# Aux_Board_V1.net
KiCad netlist of a schematic drawn in EAGLE
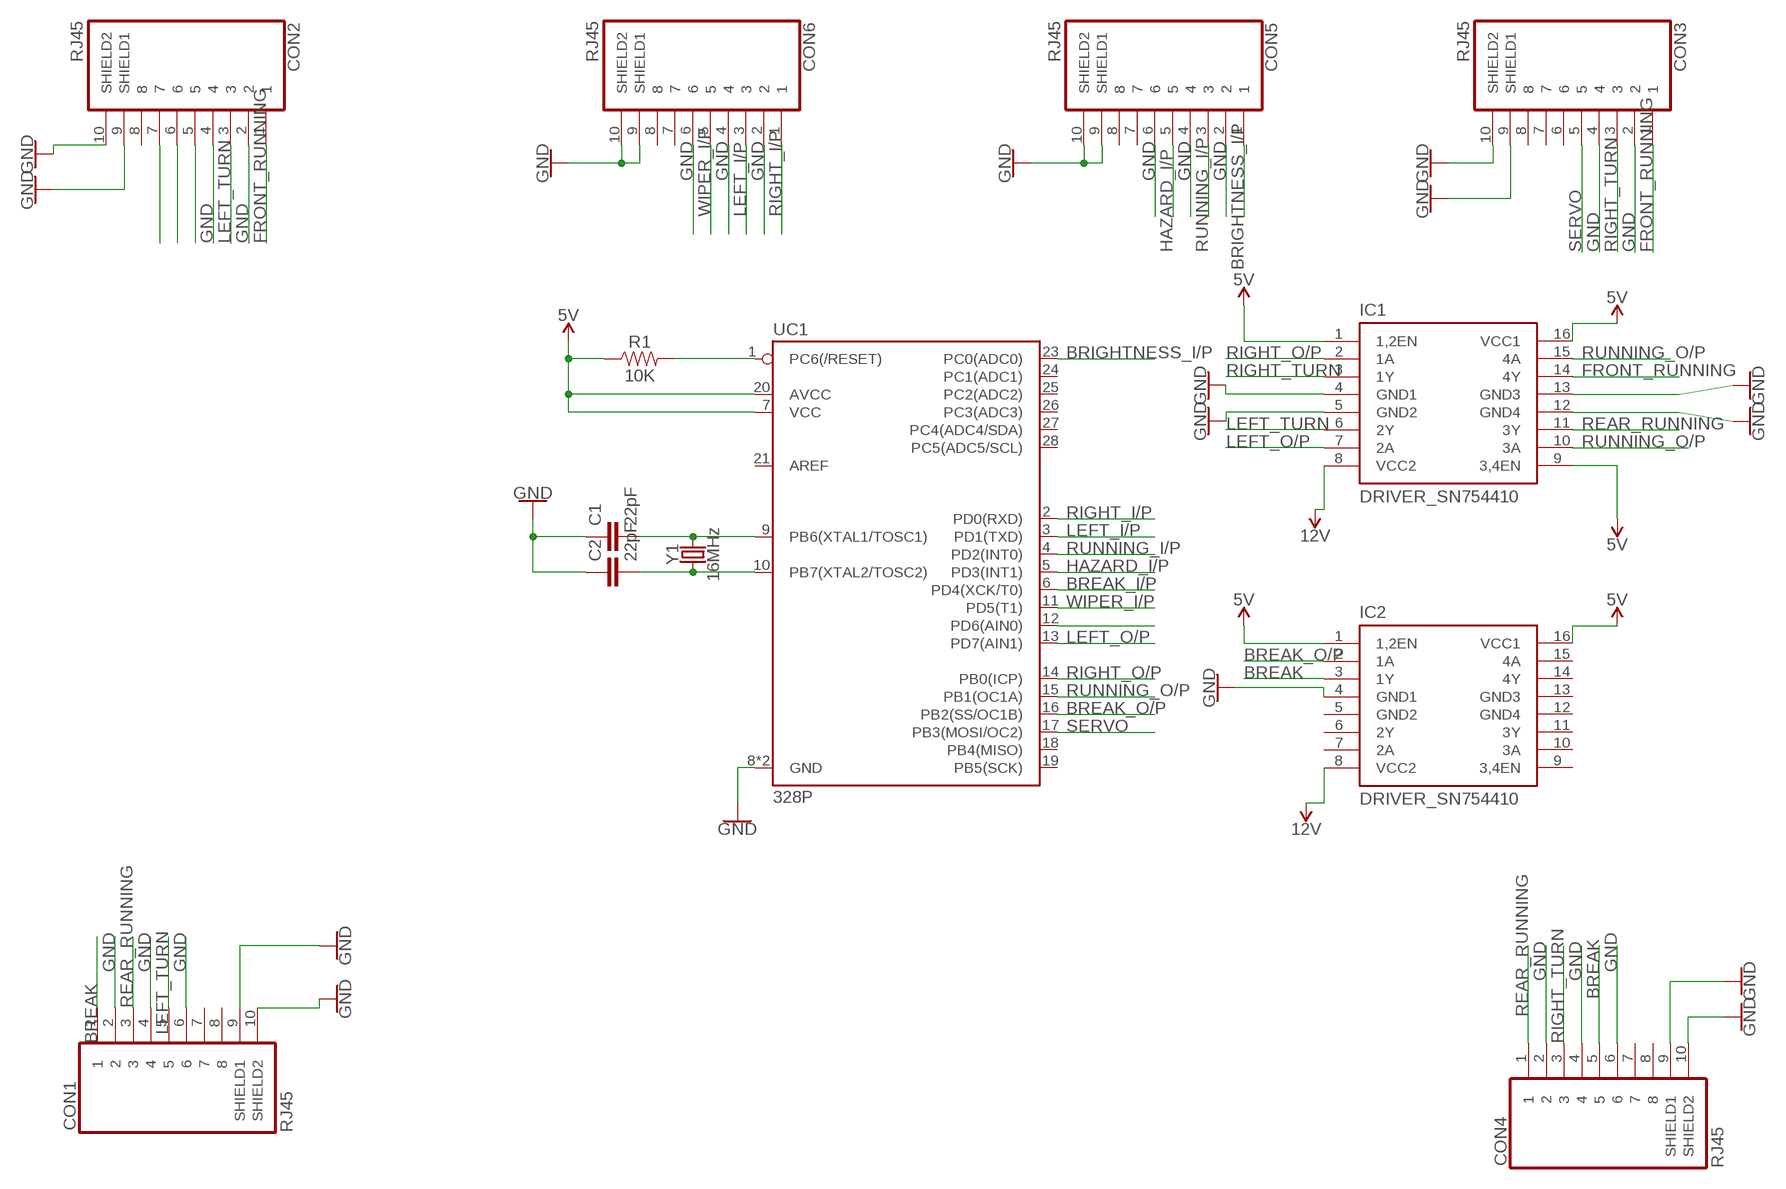
[diagram p0: schematic, sheet 1]

(export (version "E")
  (design (tool "Eeschema 10.0.6"))
  (components
    (comp (ref "C1")
      (value "22pF")
      (footprint "eagle-import:0805")
      (libsource (lib "eagle-import") (part "CAPACITOR_0805"))
    )
    (comp (ref "C2")
      (value "22pF")
      (footprint "eagle-import:0805")
      (libsource (lib "eagle-import") (part "CAPACITOR_0805"))
    )
    (comp (ref "CON1")
      (value "RJ45")
      (footprint "eagle-import:RJ45")
      (libsource (lib "eagle-import") (part "RJ45"))
    )
    (comp (ref "CON2")
      (value "RJ45")
      (footprint "eagle-import:RJ45")
      (libsource (lib "eagle-import") (part "RJ45"))
    )
    (comp (ref "CON3")
      (value "RJ45")
      (footprint "eagle-import:RJ45")
      (libsource (lib "eagle-import") (part "RJ45"))
    )
    (comp (ref "CON4")
      (value "RJ45")
      (footprint "eagle-import:RJ45")
      (libsource (lib "eagle-import") (part "RJ45"))
    )
    (comp (ref "CON5")
      (value "RJ45")
      (footprint "eagle-import:RJ45")
      (libsource (lib "eagle-import") (part "RJ45"))
    )
    (comp (ref "CON6")
      (value "RJ45")
      (footprint "eagle-import:RJ45")
      (libsource (lib "eagle-import") (part "RJ45"))
    )
    (comp (ref "IC1")
      (value "DRIVER_SN754410")
      (footprint "eagle-import:DIP16")
      (libsource (lib "eagle-import") (part "DRIVER_SN754410"))
    )
    (comp (ref "IC2")
      (value "DRIVER_SN754410")
      (footprint "eagle-import:DIP16")
      (libsource (lib "eagle-import") (part "DRIVER_SN754410"))
    )
    (comp (ref "R1")
      (value "10K")
      (footprint "eagle-import:0805")
      (libsource (lib "eagle-import") (part "RESISTOR_0805"))
    )
    (comp (ref "UC1")
      (value "328P")
      (footprint "eagle-import:DIP28")
      (libsource (lib "eagle-import") (part "ATMEGA328P_DIP28"))
    )
    (comp (ref "Y1")
      (value "16MHz")
      (footprint "eagle-import:HC49US")
      (libsource (lib "eagle-import") (part "CRYSTAL-16MHZPTH-HC49US"))
    )
  )
  (nets
    (net (code "1") (name "/BREAK") (class "Default")
      (node (ref "CON1") (pin "1") (pinfunction "1_1") (pintype "passive"))
      (node (ref "CON4") (pin "5") (pinfunction "5_5") (pintype "passive"))
      (node (ref "IC2") (pin "3") (pinfunction "1Y_3") (pintype "bidirectional"))
    )
    (net (code "2") (name "/BREAK_I{slash}P") (class "Default")
      (node (ref "UC1") (pin "6") (pinfunction "PD4(XCK/T0)_6") (pintype "bidirectional"))
    )
    (net (code "3") (name "/BREAK_O{slash}P") (class "Default")
      (node (ref "IC2") (pin "2") (pinfunction "1A_2") (pintype "bidirectional"))
      (node (ref "UC1") (pin "16") (pinfunction "PB2(SS/OC1B)_16") (pintype "bidirectional"))
    )
    (net (code "4") (name "/BRIGHTNESS_I{slash}P") (class "Default")
      (node (ref "CON5") (pin "1") (pinfunction "1_1") (pintype "passive"))
      (node (ref "UC1") (pin "23") (pinfunction "PC0(ADC0)_23") (pintype "bidirectional"))
    )
    (net (code "5") (name "/FRONT_RUNNING") (class "Default")
      (node (ref "CON2") (pin "1") (pinfunction "1_1") (pintype "passive"))
      (node (ref "CON3") (pin "1") (pinfunction "1_1") (pintype "passive"))
      (node (ref "IC1") (pin "14") (pinfunction "4Y_14") (pintype "bidirectional"))
    )
    (net (code "6") (name "/HAZARD_I{slash}P") (class "Default")
      (node (ref "CON5") (pin "5") (pinfunction "5_5") (pintype "passive"))
      (node (ref "UC1") (pin "5") (pinfunction "PD3(INT1)_5") (pintype "bidirectional"))
    )
    (net (code "7") (name "/LEFT_I{slash}P") (class "Default")
      (node (ref "CON6") (pin "3") (pinfunction "3_3") (pintype "passive"))
      (node (ref "UC1") (pin "3") (pinfunction "PD1(TXD)_3") (pintype "bidirectional"))
    )
    (net (code "8") (name "/LEFT_O{slash}P") (class "Default")
      (node (ref "IC1") (pin "7") (pinfunction "2A_7") (pintype "bidirectional"))
      (node (ref "UC1") (pin "13") (pinfunction "PD7(AIN1)_13") (pintype "bidirectional"))
    )
    (net (code "9") (name "/LEFT_TURN") (class "Default")
      (node (ref "CON1") (pin "5") (pinfunction "5_5") (pintype "passive"))
      (node (ref "CON2") (pin "3") (pinfunction "3_3") (pintype "passive"))
      (node (ref "IC1") (pin "6") (pinfunction "2Y_6") (pintype "bidirectional"))
    )
    (net (code "10") (name "/REAR_RUNNING") (class "Default")
      (node (ref "CON1") (pin "3") (pinfunction "3_3") (pintype "passive"))
      (node (ref "CON4") (pin "1") (pinfunction "1_1") (pintype "passive"))
      (node (ref "IC1") (pin "11") (pinfunction "3Y_11") (pintype "bidirectional"))
    )
    (net (code "11") (name "/RIGHT_I{slash}P") (class "Default")
      (node (ref "CON6") (pin "1") (pinfunction "1_1") (pintype "passive"))
      (node (ref "UC1") (pin "2") (pinfunction "PD0(RXD)_2") (pintype "bidirectional"))
    )
    (net (code "12") (name "/RIGHT_O{slash}P") (class "Default")
      (node (ref "IC1") (pin "2") (pinfunction "1A_2") (pintype "bidirectional"))
      (node (ref "UC1") (pin "14") (pinfunction "PB0(ICP)_14") (pintype "bidirectional"))
    )
    (net (code "13") (name "/RIGHT_TURN") (class "Default")
      (node (ref "CON3") (pin "3") (pinfunction "3_3") (pintype "passive"))
      (node (ref "CON4") (pin "3") (pinfunction "3_3") (pintype "passive"))
      (node (ref "IC1") (pin "3") (pinfunction "1Y_3") (pintype "bidirectional"))
    )
    (net (code "14") (name "/RUNNING_I{slash}P") (class "Default")
      (node (ref "CON5") (pin "3") (pinfunction "3_3") (pintype "passive"))
      (node (ref "UC1") (pin "4") (pinfunction "PD2(INT0)_4") (pintype "bidirectional"))
    )
    (net (code "15") (name "/RUNNING_O{slash}P") (class "Default")
      (node (ref "IC1") (pin "10") (pinfunction "3A_10") (pintype "bidirectional"))
      (node (ref "IC1") (pin "15") (pinfunction "4A_15") (pintype "bidirectional"))
      (node (ref "UC1") (pin "15") (pinfunction "PB1(OC1A)_15") (pintype "bidirectional"))
    )
    (net (code "16") (name "/SERVO") (class "Default")
      (node (ref "CON3") (pin "5") (pinfunction "5_5") (pintype "passive"))
      (node (ref "UC1") (pin "17") (pinfunction "PB3(MOSI/OC2)_17") (pintype "bidirectional"))
    )
    (net (code "17") (name "/WIPER_I{slash}P") (class "Default")
      (node (ref "CON6") (pin "5") (pinfunction "5_5") (pintype "passive"))
      (node (ref "UC1") (pin "11") (pinfunction "PD5(T1)_11") (pintype "bidirectional"))
    )
    (net (code "18") (name "5V") (class "Default")
      (node (ref "IC1") (pin "1") (pinfunction "1,2EN_1") (pintype "bidirectional"))
      (node (ref "IC1") (pin "16") (pinfunction "VCC1_16") (pintype "bidirectional"))
      (node (ref "IC1") (pin "9") (pinfunction "3,4EN_9") (pintype "bidirectional"))
      (node (ref "IC2") (pin "1") (pinfunction "1,2EN_1") (pintype "bidirectional"))
      (node (ref "IC2") (pin "16") (pinfunction "VCC1_16") (pintype "bidirectional"))
      (node (ref "R1") (pin "1") (pinfunction "1_1") (pintype "passive"))
      (node (ref "UC1") (pin "20") (pinfunction "AVCC_20") (pintype "bidirectional"))
      (node (ref "UC1") (pin "7") (pinfunction "VCC_7") (pintype "bidirectional"))
    )
    (net (code "19") (name "12V") (class "Default")
      (node (ref "IC1") (pin "8") (pinfunction "VCC2_8") (pintype "bidirectional"))
      (node (ref "IC2") (pin "8") (pinfunction "VCC2_8") (pintype "bidirectional"))
    )
    (net (code "20") (name "GND") (class "Default")
      (node (ref "C1") (pin "1") (pinfunction "1_1") (pintype "passive"))
      (node (ref "C2") (pin "1") (pinfunction "1_1") (pintype "passive"))
      (node (ref "CON1") (pin "10") (pinfunction "SHIELD2_10") (pintype "passive"))
      (node (ref "CON1") (pin "2") (pinfunction "2_2") (pintype "passive"))
      (node (ref "CON1") (pin "4") (pinfunction "4_4") (pintype "passive"))
      (node (ref "CON1") (pin "6") (pinfunction "6_6") (pintype "passive"))
      (node (ref "CON1") (pin "9") (pinfunction "SHIELD1_9") (pintype "passive"))
      (node (ref "CON2") (pin "10") (pinfunction "SHIELD2_10") (pintype "passive"))
      (node (ref "CON2") (pin "2") (pinfunction "2_2") (pintype "passive"))
      (node (ref "CON2") (pin "4") (pinfunction "4_4") (pintype "passive"))
      (node (ref "CON2") (pin "9") (pinfunction "SHIELD1_9") (pintype "passive"))
      (node (ref "CON3") (pin "10") (pinfunction "SHIELD2_10") (pintype "passive"))
      (node (ref "CON3") (pin "2") (pinfunction "2_2") (pintype "passive"))
      (node (ref "CON3") (pin "4") (pinfunction "4_4") (pintype "passive"))
      (node (ref "CON3") (pin "9") (pinfunction "SHIELD1_9") (pintype "passive"))
      (node (ref "CON4") (pin "10") (pinfunction "SHIELD2_10") (pintype "passive"))
      (node (ref "CON4") (pin "2") (pinfunction "2_2") (pintype "passive"))
      (node (ref "CON4") (pin "4") (pinfunction "4_4") (pintype "passive"))
      (node (ref "CON4") (pin "6") (pinfunction "6_6") (pintype "passive"))
      (node (ref "CON4") (pin "9") (pinfunction "SHIELD1_9") (pintype "passive"))
      (node (ref "CON5") (pin "10") (pinfunction "SHIELD2_10") (pintype "passive"))
      (node (ref "CON5") (pin "2") (pinfunction "2_2") (pintype "passive"))
      (node (ref "CON5") (pin "4") (pinfunction "4_4") (pintype "passive"))
      (node (ref "CON5") (pin "6") (pinfunction "6_6") (pintype "passive"))
      (node (ref "CON5") (pin "9") (pinfunction "SHIELD1_9") (pintype "passive"))
      (node (ref "CON6") (pin "10") (pinfunction "SHIELD2_10") (pintype "passive"))
      (node (ref "CON6") (pin "2") (pinfunction "2_2") (pintype "passive"))
      (node (ref "CON6") (pin "4") (pinfunction "4_4") (pintype "passive"))
      (node (ref "CON6") (pin "6") (pinfunction "6_6") (pintype "passive"))
      (node (ref "CON6") (pin "9") (pinfunction "SHIELD1_9") (pintype "passive"))
      (node (ref "IC1") (pin "12") (pinfunction "GND4_12") (pintype "bidirectional"))
      (node (ref "IC1") (pin "13") (pinfunction "GND3_13") (pintype "bidirectional"))
      (node (ref "IC1") (pin "4") (pinfunction "GND1_4") (pintype "bidirectional"))
      (node (ref "IC1") (pin "5") (pinfunction "GND2_5") (pintype "bidirectional"))
      (node (ref "IC2") (pin "4") (pinfunction "GND1_4") (pintype "bidirectional"))
      (node (ref "UC1") (pin "22") (pinfunction "GND_22") (pintype "bidirectional"))
      (node (ref "UC1") (pin "8") (pinfunction "GND_8") (pintype "bidirectional"))
    )
    (net (code "21") (name "Net-(UC1-PB6(XTAL1{slash}TOSC1))") (class "Default")
      (node (ref "C1") (pin "2") (pinfunction "2_2") (pintype "passive"))
      (node (ref "UC1") (pin "9") (pinfunction "PB6(XTAL1/TOSC1)_9") (pintype "bidirectional"))
      (node (ref "Y1") (pin "2") (pinfunction "2_2") (pintype "passive"))
    )
    (net (code "22") (name "Net-(UC1-PB7(XTAL2{slash}TOSC2))") (class "Default")
      (node (ref "C2") (pin "2") (pinfunction "2_2") (pintype "passive"))
      (node (ref "UC1") (pin "10") (pinfunction "PB7(XTAL2/TOSC2)_10") (pintype "bidirectional"))
      (node (ref "Y1") (pin "1") (pinfunction "1_1") (pintype "passive"))
    )
    (net (code "23") (name "Net-(UC1-PC6({slash}RESET))") (class "Default")
      (node (ref "R1") (pin "2") (pinfunction "2_2") (pintype "passive"))
      (node (ref "UC1") (pin "1") (pinfunction "PC6(/RESET)_1") (pintype "bidirectional"))
    )
    (net (code "24") (name "unconnected-(CON1-Pad7)") (class "Default")
      (node (ref "CON1") (pin "7") (pinfunction "7_7") (pintype "passive"))
    )
    (net (code "25") (name "unconnected-(CON1-Pad8)") (class "Default")
      (node (ref "CON1") (pin "8") (pinfunction "8_8") (pintype "passive"))
    )
    (net (code "26") (name "unconnected-(CON2-Pad5)") (class "Default")
      (node (ref "CON2") (pin "5") (pinfunction "5_5") (pintype "passive"))
    )
    (net (code "27") (name "unconnected-(CON2-Pad6)") (class "Default")
      (node (ref "CON2") (pin "6") (pinfunction "6_6") (pintype "passive"))
    )
    (net (code "28") (name "unconnected-(CON2-Pad7)") (class "Default")
      (node (ref "CON2") (pin "7") (pinfunction "7_7") (pintype "passive"))
    )
    (net (code "29") (name "unconnected-(CON2-Pad8)") (class "Default")
      (node (ref "CON2") (pin "8") (pinfunction "8_8") (pintype "passive"))
    )
    (net (code "30") (name "unconnected-(CON3-Pad6)") (class "Default")
      (node (ref "CON3") (pin "6") (pinfunction "6_6") (pintype "passive"))
    )
    (net (code "31") (name "unconnected-(CON3-Pad7)") (class "Default")
      (node (ref "CON3") (pin "7") (pinfunction "7_7") (pintype "passive"))
    )
    (net (code "32") (name "unconnected-(CON3-Pad8)") (class "Default")
      (node (ref "CON3") (pin "8") (pinfunction "8_8") (pintype "passive"))
    )
    (net (code "33") (name "unconnected-(CON4-Pad7)") (class "Default")
      (node (ref "CON4") (pin "7") (pinfunction "7_7") (pintype "passive"))
    )
    (net (code "34") (name "unconnected-(CON4-Pad8)") (class "Default")
      (node (ref "CON4") (pin "8") (pinfunction "8_8") (pintype "passive"))
    )
    (net (code "35") (name "unconnected-(CON5-Pad7)") (class "Default")
      (node (ref "CON5") (pin "7") (pinfunction "7_7") (pintype "passive"))
    )
    (net (code "36") (name "unconnected-(CON5-Pad8)") (class "Default")
      (node (ref "CON5") (pin "8") (pinfunction "8_8") (pintype "passive"))
    )
    (net (code "37") (name "unconnected-(CON6-Pad7)") (class "Default")
      (node (ref "CON6") (pin "7") (pinfunction "7_7") (pintype "passive"))
    )
    (net (code "38") (name "unconnected-(CON6-Pad8)") (class "Default")
      (node (ref "CON6") (pin "8") (pinfunction "8_8") (pintype "passive"))
    )
    (net (code "39") (name "unconnected-(IC2-2A-Pad7)") (class "Default")
      (node (ref "IC2") (pin "7") (pinfunction "2A_7") (pintype "bidirectional"))
    )
    (net (code "40") (name "unconnected-(IC2-2Y-Pad6)") (class "Default")
      (node (ref "IC2") (pin "6") (pinfunction "2Y_6") (pintype "bidirectional"))
    )
    (net (code "41") (name "unconnected-(IC2-3,4EN-Pad9)") (class "Default")
      (node (ref "IC2") (pin "9") (pinfunction "3,4EN_9") (pintype "bidirectional"))
    )
    (net (code "42") (name "unconnected-(IC2-3A-Pad10)") (class "Default")
      (node (ref "IC2") (pin "10") (pinfunction "3A_10") (pintype "bidirectional"))
    )
    (net (code "43") (name "unconnected-(IC2-3Y-Pad11)") (class "Default")
      (node (ref "IC2") (pin "11") (pinfunction "3Y_11") (pintype "bidirectional"))
    )
    (net (code "44") (name "unconnected-(IC2-4A-Pad15)") (class "Default")
      (node (ref "IC2") (pin "15") (pinfunction "4A_15") (pintype "bidirectional"))
    )
    (net (code "45") (name "unconnected-(IC2-4Y-Pad14)") (class "Default")
      (node (ref "IC2") (pin "14") (pinfunction "4Y_14") (pintype "bidirectional"))
    )
    (net (code "46") (name "unconnected-(IC2-GND2-Pad5)") (class "Default")
      (node (ref "IC2") (pin "5") (pinfunction "GND2_5") (pintype "bidirectional"))
    )
    (net (code "47") (name "unconnected-(IC2-GND3-Pad13)") (class "Default")
      (node (ref "IC2") (pin "13") (pinfunction "GND3_13") (pintype "bidirectional"))
    )
    (net (code "48") (name "unconnected-(IC2-GND4-Pad12)") (class "Default")
      (node (ref "IC2") (pin "12") (pinfunction "GND4_12") (pintype "bidirectional"))
    )
    (net (code "49") (name "unconnected-(UC1-AREF-Pad21)") (class "Default")
      (node (ref "UC1") (pin "21") (pinfunction "AREF_21") (pintype "bidirectional"))
    )
    (net (code "50") (name "unconnected-(UC1-PB4(MISO)-Pad18)") (class "Default")
      (node (ref "UC1") (pin "18") (pinfunction "PB4(MISO)_18") (pintype "bidirectional"))
    )
    (net (code "51") (name "unconnected-(UC1-PB5(SCK)-Pad19)") (class "Default")
      (node (ref "UC1") (pin "19") (pinfunction "PB5(SCK)_19") (pintype "bidirectional"))
    )
    (net (code "52") (name "unconnected-(UC1-PC1(ADC1)-Pad24)") (class "Default")
      (node (ref "UC1") (pin "24") (pinfunction "PC1(ADC1)_24") (pintype "bidirectional"))
    )
    (net (code "53") (name "unconnected-(UC1-PC2(ADC2)-Pad25)") (class "Default")
      (node (ref "UC1") (pin "25") (pinfunction "PC2(ADC2)_25") (pintype "bidirectional"))
    )
    (net (code "54") (name "unconnected-(UC1-PC3(ADC3)-Pad26)") (class "Default")
      (node (ref "UC1") (pin "26") (pinfunction "PC3(ADC3)_26") (pintype "bidirectional"))
    )
    (net (code "55") (name "unconnected-(UC1-PC4(ADC4{slash}SDA)-Pad27)") (class "Default")
      (node (ref "UC1") (pin "27") (pinfunction "PC4(ADC4/SDA)_27") (pintype "bidirectional"))
    )
    (net (code "56") (name "unconnected-(UC1-PC5(ADC5{slash}SCL)-Pad28)") (class "Default")
      (node (ref "UC1") (pin "28") (pinfunction "PC5(ADC5/SCL)_28") (pintype "bidirectional"))
    )
    (net (code "57") (name "unconnected-(UC1-PD6(AIN0)-Pad12)") (class "Default")
      (node (ref "UC1") (pin "12") (pinfunction "PD6(AIN0)_12") (pintype "bidirectional"))
    )
  )
)
